# SirenController.net
KiCad netlist of a schematic drawn in EAGLE
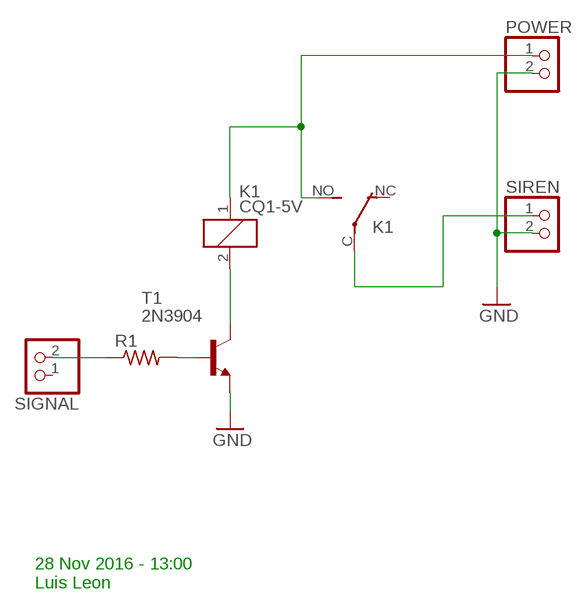
[diagram p0: schematic, sheet 1]

(export (version "E")
  (design (tool "Eeschema 10.0.6"))
  (components
    (comp (ref "K1")
      (value "CQ1-5V")
      (footprint "eagle-import:CQ1")
      (libsource (lib "eagle-import") (part "CQ1-12V"))
    )
    (comp (ref "POWER")
      (value "PINHD-1X2")
      (footprint "eagle-import:1X02")
      (libsource (lib "eagle-import") (part "PINHD-1X2"))
    )
    (comp (ref "R1")
      (value "R-US_0309/10")
      (footprint "eagle-import:0309_10")
      (libsource (lib "eagle-import") (part "R-US_0309/10"))
    )
    (comp (ref "SIGNAL")
      (value "PINHD-1X2")
      (footprint "eagle-import:1X02")
      (libsource (lib "eagle-import") (part "PINHD-1X2"))
    )
    (comp (ref "SIREN")
      (value "PINHD-1X2")
      (footprint "eagle-import:1X02")
      (libsource (lib "eagle-import") (part "PINHD-1X2"))
    )
    (comp (ref "T1")
      (value "2N3904")
      (footprint "eagle-import:TO92")
      (libsource (lib "eagle-import") (part "2N3904"))
    )
  )
  (nets
    (net (code "1") (name "GND") (class "Default")
      (node (ref "POWER") (pin "2") (pinfunction "2_2") (pintype "passive"))
      (node (ref "SIREN") (pin "2") (pinfunction "2_2") (pintype "passive"))
      (node (ref "T1") (pin "3") (pinfunction "E_3") (pintype "passive"))
    )
    (net (code "2") (name "Net-(K1B-P)") (class "Default")
      (node (ref "K1") (pin "C") (pinfunction "P_C") (pintype "passive"))
      (node (ref "SIREN") (pin "1") (pinfunction "1_1") (pintype "passive"))
    )
    (net (code "3") (name "Net-(K1B-S)") (class "Default")
      (node (ref "K1") (pin "1") (pinfunction "1_1") (pintype "passive"))
      (node (ref "K1") (pin "NO") (pinfunction "S_NO") (pintype "passive"))
      (node (ref "POWER") (pin "1") (pinfunction "1_1") (pintype "passive"))
    )
    (net (code "4") (name "Net-(R1-Pad1)") (class "Default")
      (node (ref "R1") (pin "1") (pinfunction "1_1") (pintype "passive"))
      (node (ref "SIGNAL") (pin "2") (pinfunction "2_2") (pintype "passive"))
    )
    (net (code "5") (name "Net-(T1-B)") (class "Default")
      (node (ref "R1") (pin "2") (pinfunction "2_2") (pintype "passive"))
      (node (ref "T1") (pin "2") (pinfunction "B_2") (pintype "passive"))
    )
    (net (code "6") (name "Net-(T1-C)") (class "Default")
      (node (ref "K1") (pin "2") (pinfunction "2_2") (pintype "passive"))
      (node (ref "T1") (pin "1") (pinfunction "C_1") (pintype "passive"))
    )
    (net (code "7") (name "unconnected-(K1B-O-PadNC)") (class "Default")
      (node (ref "K1") (pin "NC") (pinfunction "O_NC") (pintype "passive"))
    )
    (net (code "8") (name "unconnected-(SIGNAL-Pad1)") (class "Default")
      (node (ref "SIGNAL") (pin "1") (pinfunction "1_1") (pintype "passive"))
    )
  )
)
